# POWER.net
KiCad netlist of a schematic drawn in Altium Designer
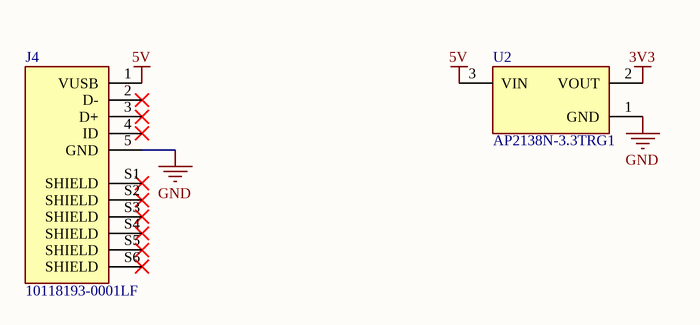
[diagram p0: POWER.SchDoc]

(export (version "E")
  (design (tool "Eeschema 10.0.6"))
  (components
    (comp (ref "J4")
      (value "10118193-0001LF")
      (footprint "FCI_10118193-0001LF")
      (description "USB - micro B USB 2.0 Receptacle Connector 5 Position Surface Mount, Right Angle; Through Hole")
      (fields (field (name "MF") "Amphenol ICC"))
      (libsource (lib "KVM Library") (part "10118193-0001LF"))
    )
    (comp (ref "U2")
      (value "AP2138N-3.3TRG1")
      (footprint "FP-SOT23-MFG")
      (description "IC REG LINEAR 3.3V 250MA SOT23-3")
      (libsource (lib "KVM Library") (part "AP2138N-3.3TRG1"))
    )
  )
  (nets
    (net (code "1") (name "3V3") (class "Default")
      (node (ref "U2") (pin "2") (pinfunction "VOUT_2") (pintype "power_in"))
    )
    (net (code "2") (name "5V") (class "Default")
      (node (ref "J4") (pin "1") (pinfunction "VUSB_1") (pintype "passive"))
      (node (ref "U2") (pin "3") (pinfunction "VIN_3") (pintype "power_in"))
    )
    (net (code "3") (name "GND") (class "Default")
      (node (ref "J4") (pin "5") (pinfunction "GND_5") (pintype "passive"))
      (node (ref "U2") (pin "1") (pinfunction "GND_1") (pintype "power_in"))
    )
    (net (code "4") (name "unconnected-(J4-D+-Pad3)") (class "Default")
      (node (ref "J4") (pin "3") (pinfunction "D+_3") (pintype "passive+no_connect"))
    )
    (net (code "5") (name "unconnected-(J4-D--Pad2)") (class "Default")
      (node (ref "J4") (pin "2") (pinfunction "D-_2") (pintype "passive+no_connect"))
    )
    (net (code "6") (name "unconnected-(J4-ID-Pad4)") (class "Default")
      (node (ref "J4") (pin "4") (pinfunction "ID_4") (pintype "passive+no_connect"))
    )
    (net (code "7") (name "unconnected-(J4-SHIELD-PadS1)") (class "Default")
      (node (ref "J4") (pin "S1") (pinfunction "SHIELD_S1") (pintype "passive+no_connect"))
    )
    (net (code "8") (name "unconnected-(J4-SHIELD-PadS2)") (class "Default")
      (node (ref "J4") (pin "S2") (pinfunction "SHIELD_S2") (pintype "passive+no_connect"))
    )
    (net (code "9") (name "unconnected-(J4-SHIELD-PadS3)") (class "Default")
      (node (ref "J4") (pin "S3") (pinfunction "SHIELD_S3") (pintype "passive+no_connect"))
    )
    (net (code "10") (name "unconnected-(J4-SHIELD-PadS4)") (class "Default")
      (node (ref "J4") (pin "S4") (pinfunction "SHIELD_S4") (pintype "passive+no_connect"))
    )
    (net (code "11") (name "unconnected-(J4-SHIELD-PadS5)") (class "Default")
      (node (ref "J4") (pin "S5") (pinfunction "SHIELD_S5") (pintype "passive+no_connect"))
    )
    (net (code "12") (name "unconnected-(J4-SHIELD-PadS6)") (class "Default")
      (node (ref "J4") (pin "S6") (pinfunction "SHIELD_S6") (pintype "passive+no_connect"))
    )
  )
)
